# 12-Dash_Inputs.net
KiCad netlist of a schematic drawn in Altium Designer
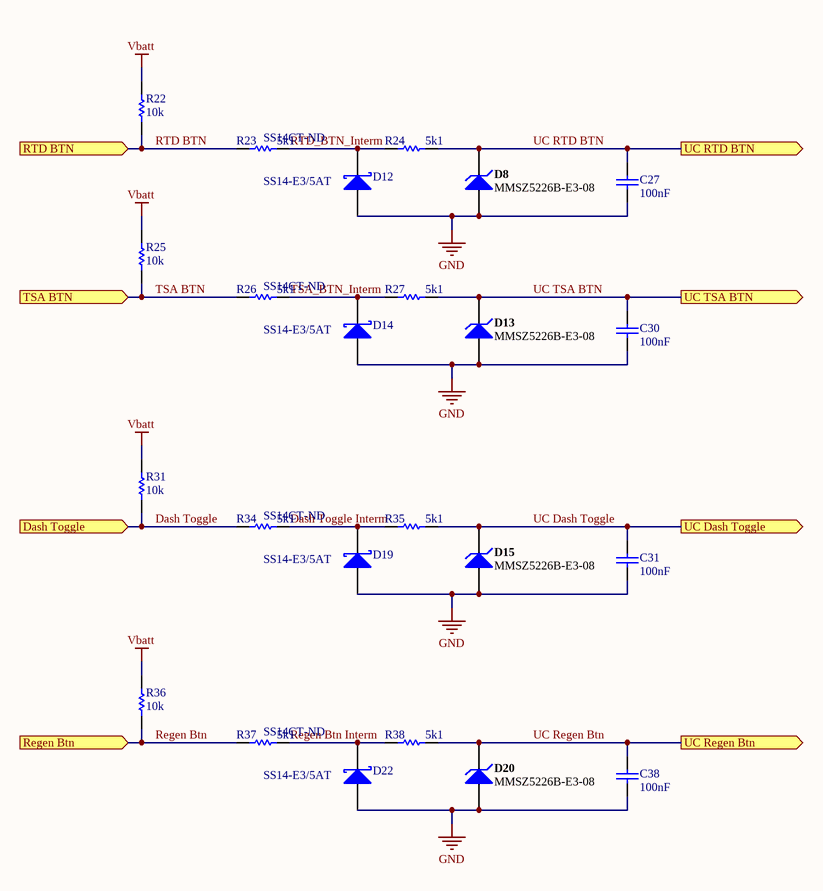
[diagram p0: 12-Dash_Inputs.SchDoc]

(export (version "E")
  (design (tool "Eeschema 10.0.6"))
  (components
    (comp (ref "C27")
      (value "100nF")
      (footprint "1608[0603]")
      (description "Capacitor")
      (fields
        (field (name "MANUFACTURER") "Yageo")
        (field (name "MANUFACTURER PART NUMBER") "CC0603KRX7R9BB104")
      )
      (libsource (lib "Miscellaneous Devices") (part "Cap"))
    )
    (comp (ref "C30")
      (value "100nF")
      (footprint "1608[0603]")
      (description "Capacitor")
      (fields
        (field (name "MANUFACTURER") "Yageo")
        (field (name "MANUFACTURER PART NUMBER") "CC0603KRX7R9BB104")
      )
      (libsource (lib "Miscellaneous Devices") (part "Cap"))
    )
    (comp (ref "C31")
      (value "100nF")
      (footprint "1608[0603]")
      (description "Capacitor")
      (fields
        (field (name "MANUFACTURER") "Yageo")
        (field (name "MANUFACTURER PART NUMBER") "CC0603KRX7R9BB104")
      )
      (libsource (lib "Miscellaneous Devices") (part "Cap"))
    )
    (comp (ref "C38")
      (value "100nF")
      (footprint "1608[0603]")
      (description "Capacitor")
      (fields
        (field (name "MANUFACTURER") "Yageo")
        (field (name "MANUFACTURER PART NUMBER") "CC0603KRX7R9BB104")
      )
      (libsource (lib "Miscellaneous Devices") (part "Cap"))
    )
    (comp (ref "D8")
      (value "MMSZ5226B-E3-08")
      (footprint "VISH-SOD-123-2_V")
      (description "Small Signal Zener Diode, 3.3 V +/- 5%, -55 to 155 degC, 2-Pin SOD-123, RoHS, Tape and Reel")
      (fields (field (name "TOLERANCE") "+/- 5%") (field (name "MANUFACTURER") "Vishay Semiconductor"))
      (libsource (lib "Altium Content Vault") (part "VISH-DZEN_A1K2-2"))
    )
    (comp (ref "D12")
      (value "SS14-E3/5AT")
      (footprint "VISH-DO-214AC-2_V")
      (fields
        (field (name "MANUFACTURER") "Vishay Semiconductor")
        (field (name "SUPPLIER PART NUMBER 1") "SS14CT-ND")
      )
      (libsource (lib "Altium Content Vault") (part "VISH-DSKY_A1K2-2"))
    )
    (comp (ref "D13")
      (value "MMSZ5226B-E3-08")
      (footprint "VISH-SOD-123-2_V")
      (description "Small Signal Zener Diode, 3.3 V +/- 5%, -55 to 155 degC, 2-Pin SOD-123, RoHS, Tape and Reel")
      (fields (field (name "TOLERANCE") "+/- 5%") (field (name "MANUFACTURER") "Vishay Semiconductor"))
      (libsource (lib "Altium Content Vault") (part "VISH-DZEN_A1K2-2"))
    )
    (comp (ref "D14")
      (value "SS14-E3/5AT")
      (footprint "VISH-DO-214AC-2_V")
      (fields
        (field (name "MANUFACTURER") "Vishay Semiconductor")
        (field (name "SUPPLIER PART NUMBER 1") "SS14CT-ND")
      )
      (libsource (lib "Altium Content Vault") (part "VISH-DSKY_A1K2-2"))
    )
    (comp (ref "D15")
      (value "MMSZ5226B-E3-08")
      (footprint "VISH-SOD-123-2_V")
      (description "Small Signal Zener Diode, 3.3 V +/- 5%, -55 to 155 degC, 2-Pin SOD-123, RoHS, Tape and Reel")
      (fields (field (name "TOLERANCE") "+/- 5%") (field (name "MANUFACTURER") "Vishay Semiconductor"))
      (libsource (lib "Altium Content Vault") (part "VISH-DZEN_A1K2-2"))
    )
    (comp (ref "D19")
      (value "SS14-E3/5AT")
      (footprint "VISH-DO-214AC-2_V")
      (fields
        (field (name "MANUFACTURER") "Vishay Semiconductor")
        (field (name "SUPPLIER PART NUMBER 1") "SS14CT-ND")
      )
      (libsource (lib "Altium Content Vault") (part "VISH-DSKY_A1K2-2"))
    )
    (comp (ref "D20")
      (value "MMSZ5226B-E3-08")
      (footprint "VISH-SOD-123-2_V")
      (description "Small Signal Zener Diode, 3.3 V +/- 5%, -55 to 155 degC, 2-Pin SOD-123, RoHS, Tape and Reel")
      (fields (field (name "TOLERANCE") "+/- 5%") (field (name "MANUFACTURER") "Vishay Semiconductor"))
      (libsource (lib "Altium Content Vault") (part "VISH-DZEN_A1K2-2"))
    )
    (comp (ref "D22")
      (value "SS14-E3/5AT")
      (footprint "VISH-DO-214AC-2_V")
      (fields
        (field (name "MANUFACTURER") "Vishay Semiconductor")
        (field (name "SUPPLIER PART NUMBER 1") "SS14CT-ND")
      )
      (libsource (lib "Altium Content Vault") (part "VISH-DSKY_A1K2-2"))
    )
    (comp (ref "R22")
      (value "10k")
      (footprint "1608[0603]")
      (description "Resistor")
      (fields
        (field (name "MANUFACTURER") "Yageo")
        (field (name "MANUFACTURER PART NUMBER") "RC0603JR-0710KL")
      )
      (libsource (lib "Miscellaneous Devices") (part "Res1"))
    )
    (comp (ref "R23")
      (value "5k1")
      (footprint "1608[0603]")
      (description "Resistor")
      (fields
        (field (name "MANUFACTURER") "Yageo")
        (field (name "MANUFACTURER PART NUMBER") "RC0603JR-075K1L")
      )
      (libsource (lib "Miscellaneous Devices") (part "Res1"))
    )
    (comp (ref "R24")
      (value "5k1")
      (footprint "1608[0603]")
      (description "Resistor")
      (fields
        (field (name "MANUFACTURER") "Yageo")
        (field (name "MANUFACTURER PART NUMBER") "RC0603JR-075K1L")
      )
      (libsource (lib "Miscellaneous Devices") (part "Res1"))
    )
    (comp (ref "R25")
      (value "10k")
      (footprint "1608[0603]")
      (description "Resistor")
      (fields
        (field (name "MANUFACTURER") "Yageo")
        (field (name "MANUFACTURER PART NUMBER") "RC0603JR-0710KL")
      )
      (libsource (lib "Miscellaneous Devices") (part "Res1"))
    )
    (comp (ref "R26")
      (value "5k1")
      (footprint "1608[0603]")
      (description "Resistor")
      (fields
        (field (name "MANUFACTURER") "Yageo")
        (field (name "MANUFACTURER PART NUMBER") "RC0603JR-075K1L")
      )
      (libsource (lib "Miscellaneous Devices") (part "Res1"))
    )
    (comp (ref "R27")
      (value "5k1")
      (footprint "1608[0603]")
      (description "Resistor")
      (fields
        (field (name "MANUFACTURER") "Yageo")
        (field (name "MANUFACTURER PART NUMBER") "RC0603JR-075K1L")
      )
      (libsource (lib "Miscellaneous Devices") (part "Res1"))
    )
    (comp (ref "R31")
      (value "10k")
      (footprint "1608[0603]")
      (description "Resistor")
      (fields
        (field (name "MANUFACTURER") "Yageo")
        (field (name "MANUFACTURER PART NUMBER") "RC0603JR-0710KL")
      )
      (libsource (lib "Miscellaneous Devices") (part "Res1"))
    )
    (comp (ref "R34")
      (value "5k1")
      (footprint "1608[0603]")
      (description "Resistor")
      (fields
        (field (name "MANUFACTURER") "Yageo")
        (field (name "MANUFACTURER PART NUMBER") "RC0603JR-075K1L")
      )
      (libsource (lib "Miscellaneous Devices") (part "Res1"))
    )
    (comp (ref "R35")
      (value "5k1")
      (footprint "1608[0603]")
      (description "Resistor")
      (fields
        (field (name "MANUFACTURER") "Yageo")
        (field (name "MANUFACTURER PART NUMBER") "RC0603JR-075K1L")
      )
      (libsource (lib "Miscellaneous Devices") (part "Res1"))
    )
    (comp (ref "R36")
      (value "10k")
      (footprint "1608[0603]")
      (description "Resistor")
      (fields
        (field (name "MANUFACTURER") "Yageo")
        (field (name "MANUFACTURER PART NUMBER") "RC0603JR-0710KL")
      )
      (libsource (lib "Miscellaneous Devices") (part "Res1"))
    )
    (comp (ref "R37")
      (value "5k1")
      (footprint "1608[0603]")
      (description "Resistor")
      (fields
        (field (name "MANUFACTURER") "Yageo")
        (field (name "MANUFACTURER PART NUMBER") "RC0603JR-075K1L")
      )
      (libsource (lib "Miscellaneous Devices") (part "Res1"))
    )
    (comp (ref "R38")
      (value "5k1")
      (footprint "1608[0603]")
      (description "Resistor")
      (fields
        (field (name "MANUFACTURER") "Yageo")
        (field (name "MANUFACTURER PART NUMBER") "RC0603JR-075K1L")
      )
      (libsource (lib "Miscellaneous Devices") (part "Res1"))
    )
  )
  (nets
    (net (code "1") (name "/Dash Toggle") (class "Default")
      (node (ref "R31") (pin "1") (pinfunction "1_1") (pintype "passive"))
      (node (ref "R34") (pin "1") (pinfunction "1_1") (pintype "passive"))
    )
    (net (code "2") (name "/Dash Toggle Interm") (class "Default")
      (node (ref "D19") (pin "2") (pinfunction "K_2") (pintype "passive"))
      (node (ref "R34") (pin "2") (pinfunction "2_2") (pintype "passive"))
      (node (ref "R35") (pin "1") (pinfunction "1_1") (pintype "passive"))
    )
    (net (code "3") (name "/RTD BTN") (class "Default")
      (node (ref "R22") (pin "1") (pinfunction "1_1") (pintype "passive"))
      (node (ref "R23") (pin "1") (pinfunction "1_1") (pintype "passive"))
    )
    (net (code "4") (name "/RTD_BTN_Interm") (class "Default")
      (node (ref "D12") (pin "2") (pinfunction "K_2") (pintype "passive"))
      (node (ref "R23") (pin "2") (pinfunction "2_2") (pintype "passive"))
      (node (ref "R24") (pin "1") (pinfunction "1_1") (pintype "passive"))
    )
    (net (code "5") (name "/Regen Btn") (class "Default")
      (node (ref "R36") (pin "1") (pinfunction "1_1") (pintype "passive"))
      (node (ref "R37") (pin "1") (pinfunction "1_1") (pintype "passive"))
    )
    (net (code "6") (name "/Regen Btn Interm") (class "Default")
      (node (ref "D22") (pin "2") (pinfunction "K_2") (pintype "passive"))
      (node (ref "R37") (pin "2") (pinfunction "2_2") (pintype "passive"))
      (node (ref "R38") (pin "1") (pinfunction "1_1") (pintype "passive"))
    )
    (net (code "7") (name "/TSA BTN") (class "Default")
      (node (ref "R25") (pin "1") (pinfunction "1_1") (pintype "passive"))
      (node (ref "R26") (pin "1") (pinfunction "1_1") (pintype "passive"))
    )
    (net (code "8") (name "/TSA_BTN_Interm") (class "Default")
      (node (ref "D14") (pin "2") (pinfunction "K_2") (pintype "passive"))
      (node (ref "R26") (pin "2") (pinfunction "2_2") (pintype "passive"))
      (node (ref "R27") (pin "1") (pinfunction "1_1") (pintype "passive"))
    )
    (net (code "9") (name "/UC Dash Toggle") (class "Default")
      (node (ref "C31") (pin "2") (pinfunction "2_2") (pintype "passive"))
      (node (ref "D15") (pin "2") (pinfunction "K_2") (pintype "passive"))
      (node (ref "R35") (pin "2") (pinfunction "2_2") (pintype "passive"))
    )
    (net (code "10") (name "/UC RTD BTN") (class "Default")
      (node (ref "C27") (pin "2") (pinfunction "2_2") (pintype "passive"))
      (node (ref "D8") (pin "2") (pinfunction "K_2") (pintype "passive"))
      (node (ref "R24") (pin "2") (pinfunction "2_2") (pintype "passive"))
    )
    (net (code "11") (name "/UC Regen Btn") (class "Default")
      (node (ref "C38") (pin "2") (pinfunction "2_2") (pintype "passive"))
      (node (ref "D20") (pin "2") (pinfunction "K_2") (pintype "passive"))
      (node (ref "R38") (pin "2") (pinfunction "2_2") (pintype "passive"))
    )
    (net (code "12") (name "/UC TSA BTN") (class "Default")
      (node (ref "C30") (pin "2") (pinfunction "2_2") (pintype "passive"))
      (node (ref "D13") (pin "2") (pinfunction "K_2") (pintype "passive"))
      (node (ref "R27") (pin "2") (pinfunction "2_2") (pintype "passive"))
    )
    (net (code "13") (name "GND") (class "Default")
      (node (ref "C27") (pin "1") (pinfunction "1_1") (pintype "passive"))
      (node (ref "C30") (pin "1") (pinfunction "1_1") (pintype "passive"))
      (node (ref "C31") (pin "1") (pinfunction "1_1") (pintype "passive"))
      (node (ref "C38") (pin "1") (pinfunction "1_1") (pintype "passive"))
      (node (ref "D12") (pin "1") (pinfunction "A_1") (pintype "passive"))
      (node (ref "D13") (pin "1") (pinfunction "A_1") (pintype "passive"))
      (node (ref "D14") (pin "1") (pinfunction "A_1") (pintype "passive"))
      (node (ref "D15") (pin "1") (pinfunction "A_1") (pintype "passive"))
      (node (ref "D19") (pin "1") (pinfunction "A_1") (pintype "passive"))
      (node (ref "D20") (pin "1") (pinfunction "A_1") (pintype "passive"))
      (node (ref "D22") (pin "1") (pinfunction "A_1") (pintype "passive"))
      (node (ref "D8") (pin "1") (pinfunction "A_1") (pintype "passive"))
    )
    (net (code "14") (name "Vbatt") (class "Default")
      (node (ref "R22") (pin "2") (pinfunction "2_2") (pintype "passive"))
      (node (ref "R25") (pin "2") (pinfunction "2_2") (pintype "passive"))
      (node (ref "R31") (pin "2") (pinfunction "2_2") (pintype "passive"))
      (node (ref "R36") (pin "2") (pinfunction "2_2") (pintype "passive"))
    )
  )
)
